# ETHERNET.net
KiCad netlist of a schematic drawn in Altium Designer
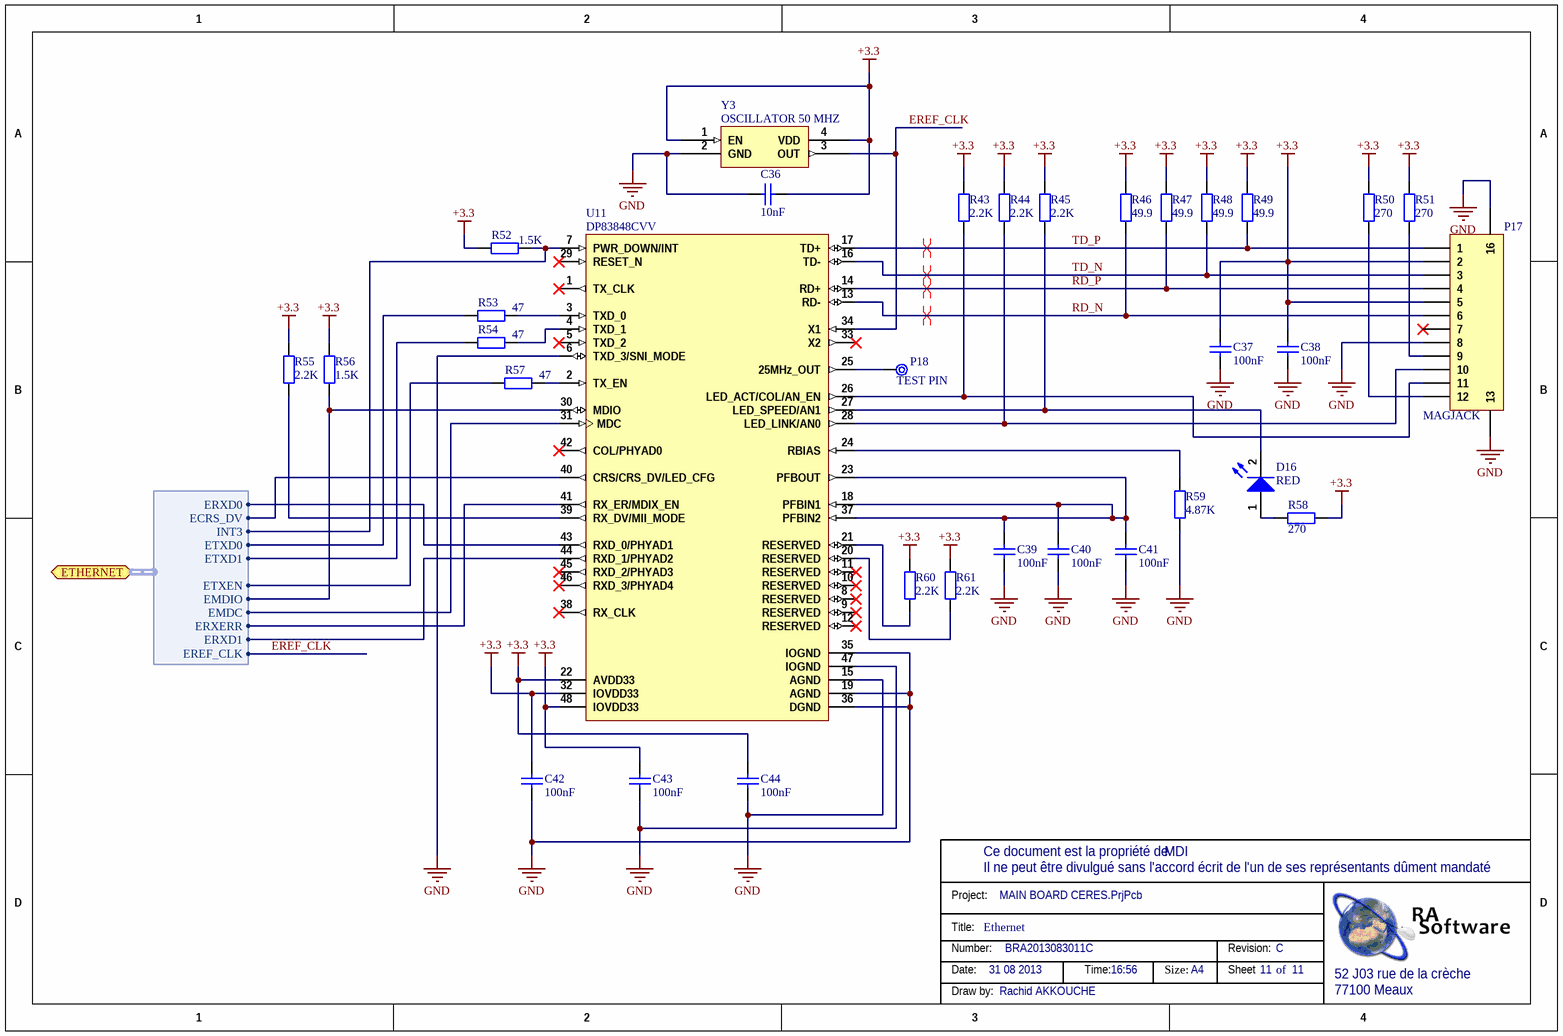
[diagram p0: ETHERNET.SchDoc]

(export (version "E")
  (design (tool "Eeschema 10.0.6"))
  (components
    (comp (ref "C36")
      (value "10nF")
      (footprint "C0805")
      (description "Capacitor")
      (fields
        (field (name "MANUFACTURER") "MULTICOMP")
        (field (name "MANUFACTURER PART NUMBER") "MC0805B103M500CT")
      )
      (libsource (lib "BRA") (part "Cap 0805 10nF"))
    )
    (comp (ref "C37")
      (value "100nF")
      (footprint "C0805")
      (description "Capacitor")
      (fields
        (field (name "MANUFACTURER") "MULTICOMP")
        (field (name "MANUFACTURER PART NUMBER") "MCCA000296")
      )
      (libsource (lib "BRA") (part "Cap 0805 100nF"))
    )
    (comp (ref "C38")
      (value "100nF")
      (footprint "C0805")
      (description "Capacitor")
      (fields
        (field (name "MANUFACTURER") "MULTICOMP")
        (field (name "MANUFACTURER PART NUMBER") "MCCA000296")
      )
      (libsource (lib "BRA") (part "Cap 0805 100nF"))
    )
    (comp (ref "C39")
      (value "100nF")
      (footprint "C0805")
      (description "Capacitor")
      (fields
        (field (name "MANUFACTURER") "MULTICOMP")
        (field (name "MANUFACTURER PART NUMBER") "MCCA000296")
      )
      (libsource (lib "BRA") (part "Cap 0805 100nF"))
    )
    (comp (ref "C40")
      (value "100nF")
      (footprint "C0805")
      (description "Capacitor")
      (fields
        (field (name "MANUFACTURER") "MULTICOMP")
        (field (name "MANUFACTURER PART NUMBER") "MCCA000296")
      )
      (libsource (lib "BRA") (part "Cap 0805 100nF"))
    )
    (comp (ref "C41")
      (value "100nF")
      (footprint "C0805")
      (description "Capacitor")
      (fields
        (field (name "MANUFACTURER") "MULTICOMP")
        (field (name "MANUFACTURER PART NUMBER") "MCCA000296")
      )
      (libsource (lib "BRA") (part "Cap 0805 100nF"))
    )
    (comp (ref "C42")
      (value "100nF")
      (footprint "C0805")
      (description "Capacitor")
      (fields
        (field (name "MANUFACTURER") "MULTICOMP")
        (field (name "MANUFACTURER PART NUMBER") "MCCA000296")
      )
      (libsource (lib "BRA") (part "Cap 0805 100nF"))
    )
    (comp (ref "C43")
      (value "100nF")
      (footprint "C0805")
      (description "Capacitor")
      (fields
        (field (name "MANUFACTURER") "MULTICOMP")
        (field (name "MANUFACTURER PART NUMBER") "MCCA000296")
      )
      (libsource (lib "BRA") (part "Cap 0805 100nF"))
    )
    (comp (ref "C44")
      (value "100nF")
      (footprint "C0805")
      (description "Capacitor")
      (fields
        (field (name "MANUFACTURER") "MULTICOMP")
        (field (name "MANUFACTURER PART NUMBER") "MCCA000296")
      )
      (libsource (lib "BRA") (part "Cap 0805 100nF"))
    )
    (comp (ref "D16")
      (value "HSMH-C190")
      (footprint "SYLANN:0603-LEDR")
      (description "Surface Mount Chip LED, Red")
      (fields
        (field (name "MANUFACTURER") "AVAGO TECHNOLOGIES")
        (field (name "MANUFACTURER PART NUMBER") "HSMH-C190.")
        (field (name "COULEUR") "RED")
        (field (name "LONGUEUR/HAUTEUR") "1.6")
      )
      (libsource (lib "Avago Optoelectronic LED") (part "HSMH-C190"))
    )
    (comp (ref "P17")
      (value "MAGJACK")
      (footprint "RJ45_8+LED")
      (description "Header, 12-Pin")
      (fields
        (field (name "MANUFACTURER") "STEWART CONNECTOR")
        (field (name "MANUFACTURER PART NUMBER") "SI-60062-F")
        (field (name "PUBLISHER") "Altium Limited")
      )
      (libsource (lib "MAIN BOARD CERES") (part "Header 12"))
    )
    (comp (ref "P18") (value "TEST PIN") (footprint "TP") (libsource (lib "UTIL_Library") (part "TEST PIN")))
    (comp (ref "R43")
      (value "2.2K")
      (footprint "R0805")
      (description "Resistor")
      (fields
        (field (name "MANUFACTURER") "MULTICOMP")
        (field (name "MANUFACTURER PART NUMBER") "MC01W080512K2")
      )
      (libsource (lib "BRA") (part "Resistor 0805 2.2K"))
    )
    (comp (ref "R44")
      (value "2.2K")
      (footprint "R0805")
      (description "Resistor")
      (fields
        (field (name "MANUFACTURER") "MULTICOMP")
        (field (name "MANUFACTURER PART NUMBER") "MC01W080512K2")
      )
      (libsource (lib "BRA") (part "Resistor 0805 2.2K"))
    )
    (comp (ref "R45")
      (value "2.2K")
      (footprint "R0805")
      (description "Resistor")
      (fields
        (field (name "MANUFACTURER") "MULTICOMP")
        (field (name "MANUFACTURER PART NUMBER") "MC01W080512K2")
      )
      (libsource (lib "BRA") (part "Resistor 0805 2.2K"))
    )
    (comp (ref "R46")
      (value "49.9")
      (footprint "R0805")
      (description "Resistor")
      (fields
        (field (name "MANUFACTURER") "MULTICOMP")
        (field (name "MANUFACTURER PART NUMBER") "MC01W0805149R9")
      )
      (libsource (lib "BRA") (part "Resistor 0805 49.9"))
    )
    (comp (ref "R47")
      (value "49.9")
      (footprint "R0805")
      (description "Resistor")
      (fields
        (field (name "MANUFACTURER") "MULTICOMP")
        (field (name "MANUFACTURER PART NUMBER") "MC01W0805149R9")
      )
      (libsource (lib "BRA") (part "Resistor 0805 49.9"))
    )
    (comp (ref "R48")
      (value "49.9")
      (footprint "R0805")
      (description "Resistor")
      (fields
        (field (name "MANUFACTURER") "MULTICOMP")
        (field (name "MANUFACTURER PART NUMBER") "MC01W0805149R9")
      )
      (libsource (lib "BRA") (part "Resistor 0805 49.9"))
    )
    (comp (ref "R49")
      (value "49.9")
      (footprint "R0805")
      (description "Resistor")
      (fields
        (field (name "MANUFACTURER") "MULTICOMP")
        (field (name "MANUFACTURER PART NUMBER") "MC01W0805149R9")
      )
      (libsource (lib "BRA") (part "Resistor 0805 49.9"))
    )
    (comp (ref "R50")
      (value "270")
      (footprint "R0805")
      (description "Resistor")
      (fields
        (field (name "MANUFACTURER") "MULTICOMP")
        (field (name "MANUFACTURER PART NUMBER") "MC01W08051270R")
      )
      (libsource (lib "BRA") (part "Resistor 0805 270"))
    )
    (comp (ref "R51")
      (value "270")
      (footprint "R0805")
      (description "Resistor")
      (fields
        (field (name "MANUFACTURER") "MULTICOMP")
        (field (name "MANUFACTURER PART NUMBER") "MC01W08051270R")
      )
      (libsource (lib "BRA") (part "Resistor 0805 270"))
    )
    (comp (ref "R52")
      (value "1.5K")
      (footprint "R0805")
      (description "Resistor")
      (fields
        (field (name "MANUFACTURER") "MULTICOMP")
        (field (name "MANUFACTURER PART NUMBER") "MC00625W040211K5")
      )
      (libsource (lib "") (part "Resistor 0805 1.5K_1"))
    )
    (comp (ref "R53")
      (value "47")
      (footprint "R0805")
      (description "Resistor")
      (fields
        (field (name "MANUFACTURER") "MULTICOMP")
        (field (name "MANUFACTURER PART NUMBER") "MC0063W0603147R")
      )
      (libsource (lib "BRA") (part "Resistor 0805 47"))
    )
    (comp (ref "R54")
      (value "47")
      (footprint "R0805")
      (description "Resistor")
      (fields
        (field (name "MANUFACTURER") "MULTICOMP")
        (field (name "MANUFACTURER PART NUMBER") "MC0063W0603147R")
      )
      (libsource (lib "BRA") (part "Resistor 0805 47"))
    )
    (comp (ref "R55")
      (value "2.2K")
      (footprint "R0805")
      (description "Resistor")
      (fields
        (field (name "MANUFACTURER") "MULTICOMP")
        (field (name "MANUFACTURER PART NUMBER") "MC01W080512K2")
      )
      (libsource (lib "BRA") (part "Resistor 0805 2.2K"))
    )
    (comp (ref "R56")
      (value "1.5K")
      (footprint "R0805")
      (description "Resistor")
      (fields
        (field (name "MANUFACTURER") "MULTICOMP")
        (field (name "MANUFACTURER PART NUMBER") "MC00625W040211K5")
      )
      (libsource (lib "BRA") (part "Resistor 0805 1.5K"))
    )
    (comp (ref "R57")
      (value "47")
      (footprint "R0805")
      (description "Resistor")
      (fields
        (field (name "MANUFACTURER") "MULTICOMP")
        (field (name "MANUFACTURER PART NUMBER") "MC0063W0603147R")
      )
      (libsource (lib "BRA") (part "Resistor 0805 47"))
    )
    (comp (ref "R58")
      (value "270")
      (footprint "R0805")
      (description "Resistor")
      (fields
        (field (name "MANUFACTURER") "MULTICOMP")
        (field (name "MANUFACTURER PART NUMBER") "MC01W08051270R")
      )
      (libsource (lib "BRA") (part "Resistor 0805 1K"))
    )
    (comp (ref "R59")
      (value "4.87K")
      (footprint "R0805")
      (description "Resistor")
      (fields
        (field (name "MANUFACTURER") "MULTICOMP")
        (field (name "MANUFACTURER PART NUMBER") "MC01W080514K87")
      )
      (libsource (lib "BRA") (part "Resistor 0805"))
    )
    (comp (ref "R60")
      (value "2.2K")
      (footprint "R0805")
      (description "Resistor")
      (fields
        (field (name "MANUFACTURER") "MULTICOMP")
        (field (name "MANUFACTURER PART NUMBER") "MC01W080512K2")
      )
      (libsource (lib "BRA") (part "Resistor 0805 2.2K"))
    )
    (comp (ref "R61")
      (value "2.2K")
      (footprint "R0805")
      (description "Resistor")
      (fields
        (field (name "MANUFACTURER") "MULTICOMP")
        (field (name "MANUFACTURER PART NUMBER") "MC01W080512K2")
      )
      (libsource (lib "BRA") (part "Resistor 0805 2.2K"))
    )
    (comp (ref "U11")
      (value "DP83848CVV")
      (footprint "LQFP48")
      (fields
        (field (name "MANUFACTURER") "National Semiconductor")
        (field (name "PUBLISHER") "Altium Limited")
      )
      (libsource (lib "NSC Interface") (part "DP83848CVV"))
    )
    (comp (ref "Y3")
      (value "OSCILLATOR 50 MHZ")
      (footprint "X3225")
      (description "50 MHZ 3.3Vdc CMOS SMD CRYSTAL CLOCK OSCILLATOR")
      (fields
        (field (name "MANUFACTURER") "ABRACON")
        (field (name "MANUFACTURER PART NUMBER") "ASE-50.000MHZ-LR-T")
      )
      (libsource (lib "BRA") (part "OSCILLLATOR"))
    )
  )
  (nets
    (net (code "2") (name "+3.3") (class "Default")
      (node (ref "C36") (pin "1") (pinfunction "1_1") (pintype "passive"))
      (node (ref "C37") (pin "1") (pinfunction "1_1") (pintype "passive"))
      (node (ref "C38") (pin "1") (pinfunction "1_1") (pintype "passive"))
      (node (ref "C42") (pin "1") (pinfunction "1_1") (pintype "passive"))
      (node (ref "C43") (pin "1") (pinfunction "1_1") (pintype "passive"))
      (node (ref "C44") (pin "1") (pinfunction "1_1") (pintype "passive"))
      (node (ref "P17") (pin "2") (pinfunction "2_2") (pintype "passive"))
      (node (ref "P17") (pin "5") (pinfunction "5_5") (pintype "passive"))
      (node (ref "R43") (pin "2") (pinfunction "2_2") (pintype "passive"))
      (node (ref "R44") (pin "2") (pinfunction "2_2") (pintype "passive"))
      (node (ref "R45") (pin "2") (pinfunction "2_2") (pintype "passive"))
      (node (ref "R46") (pin "2") (pinfunction "2_2") (pintype "passive"))
      (node (ref "R47") (pin "2") (pinfunction "2_2") (pintype "passive"))
      (node (ref "R48") (pin "2") (pinfunction "2_2") (pintype "passive"))
      (node (ref "R49") (pin "2") (pinfunction "2_2") (pintype "passive"))
      (node (ref "R50") (pin "2") (pinfunction "2_2") (pintype "passive"))
      (node (ref "R51") (pin "2") (pinfunction "2_2") (pintype "passive"))
      (node (ref "R52") (pin "2") (pinfunction "2_2") (pintype "passive"))
      (node (ref "R55") (pin "2") (pinfunction "2_2") (pintype "passive"))
      (node (ref "R56") (pin "2") (pinfunction "2_2") (pintype "passive"))
      (node (ref "R58") (pin "1") (pinfunction "1_1") (pintype "passive"))
      (node (ref "R60") (pin "2") (pinfunction "2_2") (pintype "passive"))
      (node (ref "R61") (pin "2") (pinfunction "2_2") (pintype "passive"))
      (node (ref "U11") (pin "22") (pinfunction "AVDD33_22") (pintype "power_in"))
      (node (ref "U11") (pin "32") (pinfunction "IOVDD33_32") (pintype "power_in"))
      (node (ref "U11") (pin "48") (pinfunction "IOVDD33_48") (pintype "power_in"))
      (node (ref "Y3") (pin "1") (pinfunction "EN_1") (pintype "input"))
      (node (ref "Y3") (pin "4") (pinfunction "VDD_4") (pintype "power_in"))
    )
    (net (code "3") (name "/ECRS_DV") (class "Default")
      (node (ref "U11") (pin "40") (pinfunction "CRS/CRS_DV/LED_CFG_40") (pintype "output"))
    )
    (net (code "4") (name "/EMDC") (class "Default")
      (node (ref "U11") (pin "31") (pinfunction "MDC_31") (pintype "input"))
    )
    (net (code "5") (name "/EMDIO") (class "Default")
      (node (ref "R56") (pin "1") (pinfunction "1_1") (pintype "passive"))
      (node (ref "U11") (pin "30") (pinfunction "MDIO_30") (pintype "bidirectional"))
    )
    (net (code "6") (name "/EREF_CLK") (class "Default")
      (node (ref "U11") (pin "34") (pinfunction "X1_34") (pintype "input"))
      (node (ref "Y3") (pin "3") (pinfunction "OUT_3") (pintype "output"))
    )
    (net (code "7") (name "/ERXD0") (class "Default")
      (node (ref "U11") (pin "43") (pinfunction "RXD_0/PHYAD1_43") (pintype "output"))
    )
    (net (code "8") (name "/ERXD1") (class "Default")
      (node (ref "U11") (pin "44") (pinfunction "RXD_1/PHYAD2_44") (pintype "output"))
    )
    (net (code "9") (name "/ERXERR") (class "Default")
      (node (ref "U11") (pin "41") (pinfunction "RX_ER/MDIX_EN_41") (pintype "output"))
    )
    (net (code "10") (name "/ETXD0") (class "Default")
      (node (ref "R53") (pin "2") (pinfunction "2_2") (pintype "passive"))
    )
    (net (code "11") (name "/ETXD1") (class "Default")
      (node (ref "R54") (pin "2") (pinfunction "2_2") (pintype "passive"))
    )
    (net (code "12") (name "/ETXEN") (class "Default")
      (node (ref "R57") (pin "2") (pinfunction "2_2") (pintype "passive"))
    )
    (net (code "13") (name "/INT3") (class "Default")
      (node (ref "R52") (pin "1") (pinfunction "1_1") (pintype "passive"))
      (node (ref "U11") (pin "7") (pinfunction "PWR_DOWN/INT_7") (pintype "input"))
    )
    (net (code "14") (name "/RD_N") (class "Default")
      (node (ref "P17") (pin "6") (pinfunction "6_6") (pintype "passive"))
      (node (ref "R46") (pin "1") (pinfunction "1_1") (pintype "passive"))
      (node (ref "U11") (pin "13") (pinfunction "RD-_13") (pintype "bidirectional"))
    )
    (net (code "15") (name "/RD_P") (class "Default")
      (node (ref "P17") (pin "4") (pinfunction "4_4") (pintype "passive"))
      (node (ref "R47") (pin "1") (pinfunction "1_1") (pintype "passive"))
      (node (ref "U11") (pin "14") (pinfunction "RD+_14") (pintype "bidirectional"))
    )
    (net (code "16") (name "/TD_N") (class "Default")
      (node (ref "P17") (pin "3") (pinfunction "3_3") (pintype "passive"))
      (node (ref "R48") (pin "1") (pinfunction "1_1") (pintype "passive"))
      (node (ref "U11") (pin "16") (pinfunction "TD-_16") (pintype "bidirectional"))
    )
    (net (code "17") (name "/TD_P") (class "Default")
      (node (ref "P17") (pin "1") (pinfunction "1_1") (pintype "passive"))
      (node (ref "R49") (pin "1") (pinfunction "1_1") (pintype "passive"))
      (node (ref "U11") (pin "17") (pinfunction "TD+_17") (pintype "bidirectional"))
    )
    (net (code "19") (name "GND") (class "Default")
      (node (ref "C36") (pin "2") (pinfunction "2_2") (pintype "passive"))
      (node (ref "C37") (pin "2") (pinfunction "2_2") (pintype "passive"))
      (node (ref "C38") (pin "2") (pinfunction "2_2") (pintype "passive"))
      (node (ref "C39") (pin "2") (pinfunction "2_2") (pintype "passive"))
      (node (ref "C40") (pin "2") (pinfunction "2_2") (pintype "passive"))
      (node (ref "C41") (pin "2") (pinfunction "2_2") (pintype "passive"))
      (node (ref "C42") (pin "2") (pinfunction "2_2") (pintype "passive"))
      (node (ref "C43") (pin "2") (pinfunction "2_2") (pintype "passive"))
      (node (ref "C44") (pin "2") (pinfunction "2_2") (pintype "passive"))
      (node (ref "P17") (pin "13") (pinfunction "13_13") (pintype "passive"))
      (node (ref "P17") (pin "16") (pinfunction "16_16") (pintype "passive"))
      (node (ref "P17") (pin "8") (pinfunction "8_8") (pintype "passive"))
      (node (ref "R59") (pin "1") (pinfunction "1_1") (pintype "passive"))
      (node (ref "U11") (pin "15") (pinfunction "AGND_15") (pintype "power_in"))
      (node (ref "U11") (pin "19") (pinfunction "AGND_19") (pintype "power_in"))
      (node (ref "U11") (pin "35") (pinfunction "IOGND_35") (pintype "power_in"))
      (node (ref "U11") (pin "36") (pinfunction "DGND_36") (pintype "power_in"))
      (node (ref "U11") (pin "47") (pinfunction "IOGND_47") (pintype "power_in"))
      (node (ref "U11") (pin "6") (pinfunction "TXD_3/SNI_MODE_6") (pintype "bidirectional"))
      (node (ref "Y3") (pin "2") (pinfunction "GND_2") (pintype "power_in"))
    )
    (net (code "20") (name "Net-(D16-A)") (class "Default")
      (node (ref "D16") (pin "1") (pinfunction "A_1") (pintype "passive"))
      (node (ref "R58") (pin "2") (pinfunction "2_2") (pintype "passive"))
    )
    (net (code "21") (name "Net-(D16-K)") (class "Default")
      (node (ref "D16") (pin "2") (pinfunction "K_2") (pintype "passive"))
      (node (ref "R45") (pin "1") (pinfunction "1_1") (pintype "passive"))
      (node (ref "U11") (pin "27") (pinfunction "LED_SPEED/AN1_27") (pintype "output"))
    )
    (net (code "22") (name "Net-(P17-Pad9)") (class "Default")
      (node (ref "P17") (pin "9") (pinfunction "9_9") (pintype "passive"))
      (node (ref "R51") (pin "1") (pinfunction "1_1") (pintype "passive"))
    )
    (net (code "23") (name "Net-(P17-Pad12)") (class "Default")
      (node (ref "P17") (pin "12") (pinfunction "12_12") (pintype "passive"))
      (node (ref "R50") (pin "1") (pinfunction "1_1") (pintype "passive"))
    )
    (net (code "24") (name "Net-(R60-Pad1)") (class "Default")
      (node (ref "R60") (pin "1") (pinfunction "1_1") (pintype "passive"))
      (node (ref "U11") (pin "21") (pinfunction "RESERVED_21") (pintype "bidirectional"))
    )
    (net (code "25") (name "Net-(R61-Pad1)") (class "Default")
      (node (ref "R61") (pin "1") (pinfunction "1_1") (pintype "passive"))
      (node (ref "U11") (pin "20") (pinfunction "RESERVED_20") (pintype "bidirectional"))
    )
    (net (code "26") (name "Net-(U11-25MHz_OUT)") (class "Default")
      (node (ref "P18") (pin "1") (pinfunction "1_1") (pintype "passive"))
      (node (ref "U11") (pin "25") (pinfunction "25MHz_OUT_25") (pintype "output"))
    )
    (net (code "27") (name "Net-(U11-LED_ACT{slash}COL{slash}AN_EN)") (class "Default")
      (node (ref "P17") (pin "11") (pinfunction "11_11") (pintype "passive"))
      (node (ref "R43") (pin "1") (pinfunction "1_1") (pintype "passive"))
      (node (ref "U11") (pin "26") (pinfunction "LED_ACT/COL/AN_EN_26") (pintype "output"))
    )
    (net (code "28") (name "Net-(U11-LED_LINK{slash}AN0)") (class "Default")
      (node (ref "P17") (pin "10") (pinfunction "10_10") (pintype "passive"))
      (node (ref "R44") (pin "1") (pinfunction "1_1") (pintype "passive"))
      (node (ref "U11") (pin "28") (pinfunction "LED_LINK/AN0_28") (pintype "output"))
    )
    (net (code "29") (name "Net-(U11-PFBIN1)") (class "Default")
      (node (ref "C39") (pin "1") (pinfunction "1_1") (pintype "passive"))
      (node (ref "C40") (pin "1") (pinfunction "1_1") (pintype "passive"))
      (node (ref "C41") (pin "1") (pinfunction "1_1") (pintype "passive"))
      (node (ref "U11") (pin "18") (pinfunction "PFBIN1_18") (pintype "input"))
      (node (ref "U11") (pin "23") (pinfunction "PFBOUT_23") (pintype "output"))
      (node (ref "U11") (pin "37") (pinfunction "PFBIN2_37") (pintype "input"))
    )
    (net (code "30") (name "Net-(U11-RBIAS)") (class "Default")
      (node (ref "R59") (pin "2") (pinfunction "2_2") (pintype "passive"))
      (node (ref "U11") (pin "24") (pinfunction "RBIAS_24") (pintype "input"))
    )
    (net (code "31") (name "Net-(U11-RX_DV{slash}MII_MODE)") (class "Default")
      (node (ref "R55") (pin "1") (pinfunction "1_1") (pintype "passive"))
      (node (ref "U11") (pin "39") (pinfunction "RX_DV/MII_MODE_39") (pintype "output"))
    )
    (net (code "32") (name "Net-(U11-TXD_0)") (class "Default")
      (node (ref "R53") (pin "1") (pinfunction "1_1") (pintype "passive"))
      (node (ref "U11") (pin "3") (pinfunction "TXD_0_3") (pintype "input"))
    )
    (net (code "33") (name "Net-(U11-TXD_1)") (class "Default")
      (node (ref "R54") (pin "1") (pinfunction "1_1") (pintype "passive"))
      (node (ref "U11") (pin "4") (pinfunction "TXD_1_4") (pintype "input"))
    )
    (net (code "34") (name "Net-(U11-TX_EN)") (class "Default")
      (node (ref "R57") (pin "1") (pinfunction "1_1") (pintype "passive"))
      (node (ref "U11") (pin "2") (pinfunction "TX_EN_2") (pintype "input"))
    )
    (net (code "35") (name "unconnected-(P17-Pad7)") (class "Default")
      (node (ref "P17") (pin "7") (pinfunction "7_7") (pintype "passive+no_connect"))
    )
    (net (code "36") (name "unconnected-(U11-COL{slash}PHYAD0-Pad42)") (class "Default")
      (node (ref "U11") (pin "42") (pinfunction "COL/PHYAD0_42") (pintype "output+no_connect"))
    )
    (net (code "37") (name "unconnected-(U11-RESERVED-Pad8)") (class "Default")
      (node (ref "U11") (pin "8") (pinfunction "RESERVED_8") (pintype "bidirectional+no_connect"))
    )
    (net (code "38") (name "unconnected-(U11-RESERVED-Pad9)") (class "Default")
      (node (ref "U11") (pin "9") (pinfunction "RESERVED_9") (pintype "bidirectional+no_connect"))
    )
    (net (code "39") (name "unconnected-(U11-RESERVED-Pad10)") (class "Default")
      (node (ref "U11") (pin "10") (pinfunction "RESERVED_10") (pintype "bidirectional+no_connect"))
    )
    (net (code "40") (name "unconnected-(U11-RESERVED-Pad11)") (class "Default")
      (node (ref "U11") (pin "11") (pinfunction "RESERVED_11") (pintype "bidirectional+no_connect"))
    )
    (net (code "41") (name "unconnected-(U11-RESERVED-Pad12)") (class "Default")
      (node (ref "U11") (pin "12") (pinfunction "RESERVED_12") (pintype "bidirectional+no_connect"))
    )
    (net (code "42") (name "unconnected-(U11-RESET_N-Pad29)") (class "Default")
      (node (ref "U11") (pin "29") (pinfunction "RESET_N_29") (pintype "input+no_connect"))
    )
    (net (code "43") (name "unconnected-(U11-RXD_2{slash}PHYAD3-Pad45)") (class "Default")
      (node (ref "U11") (pin "45") (pinfunction "RXD_2/PHYAD3_45") (pintype "output+no_connect"))
    )
    (net (code "44") (name "unconnected-(U11-RXD_3{slash}PHYAD4-Pad46)") (class "Default")
      (node (ref "U11") (pin "46") (pinfunction "RXD_3/PHYAD4_46") (pintype "output+no_connect"))
    )
    (net (code "45") (name "unconnected-(U11-RX_CLK-Pad38)") (class "Default")
      (node (ref "U11") (pin "38") (pinfunction "RX_CLK_38") (pintype "output+no_connect"))
    )
    (net (code "46") (name "unconnected-(U11-TXD_2-Pad5)") (class "Default")
      (node (ref "U11") (pin "5") (pinfunction "TXD_2_5") (pintype "input+no_connect"))
    )
    (net (code "47") (name "unconnected-(U11-TX_CLK-Pad1)") (class "Default")
      (node (ref "U11") (pin "1") (pinfunction "TX_CLK_1") (pintype "output+no_connect"))
    )
    (net (code "48") (name "unconnected-(U11-X2-Pad33)") (class "Default")
      (node (ref "U11") (pin "33") (pinfunction "X2_33") (pintype "output+no_connect"))
    )
  )
)
